# AtmoOrb.net
KiCad netlist of a schematic drawn in EAGLE
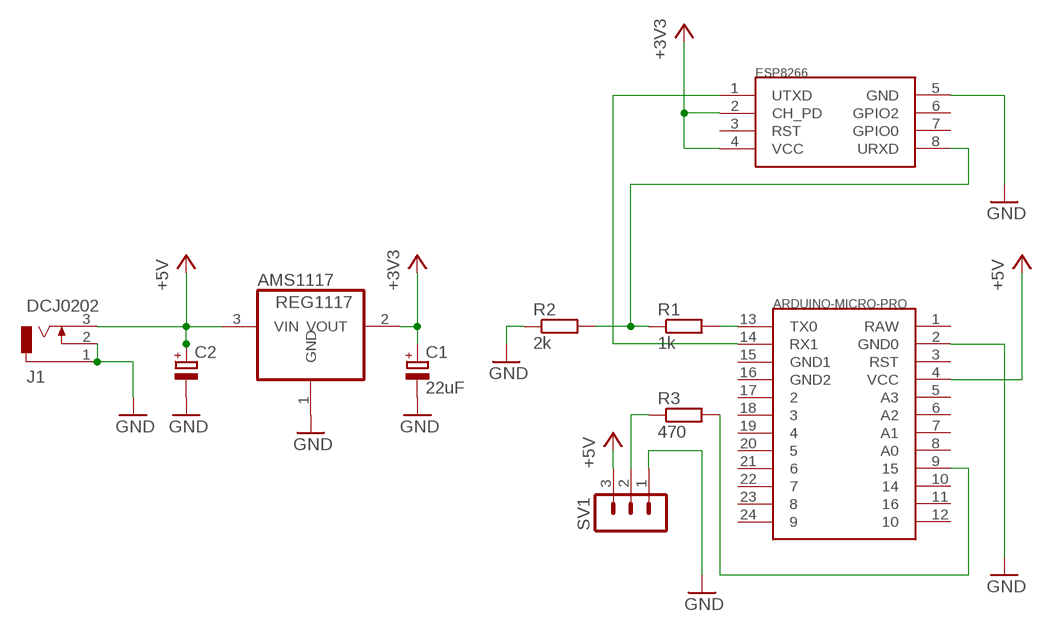
[diagram p0: schematic, sheet 1]

(export (version "E")
  (design (tool "Eeschema 10.0.6"))
  (components
    (comp (ref "AMS1117")
      (value "REG1117")
      (footprint "eagle-import:SOT223")
      (libsource (lib "eagle-import") (part "REG1117"))
    )
    (comp (ref "ARDUINO-MICRO-PRO")
      (value "ARDUINO_MICRO_PRO")
      (footprint "eagle-import:ARDUINO_MICRO_PRO")
      (libsource (lib "eagle-import") (part "ARDUINO_MICRO_PRO"))
    )
    (comp (ref "C1")
      (value "22uF")
      (footprint "eagle-import:TAP5-60")
      (libsource (lib "eagle-import") (part "CPOL-EUTAP5-60"))
    )
    (comp (ref "C2")
      (value "CPOL-EUTAP5-60")
      (footprint "eagle-import:TAP5-60")
      (libsource (lib "eagle-import") (part "CPOL-EUTAP5-60"))
    )
    (comp (ref "ESP8266")
      (value "ESP8266")
      (footprint "eagle-import:ESP8266")
      (libsource (lib "eagle-import") (part "ESP8266"))
    )
    (comp (ref "J1")
      (value "DCJ0202")
      (footprint "eagle-import:DCJ0202")
      (libsource (lib "eagle-import") (part "DCJ0202"))
    )
    (comp (ref "R1")
      (value "1k")
      (footprint "eagle-import:0207_10")
      (libsource (lib "eagle-import") (part "R-EU_0207/10"))
    )
    (comp (ref "R2")
      (value "2k")
      (footprint "eagle-import:0207_10")
      (libsource (lib "eagle-import") (part "R-EU_0207/10"))
    )
    (comp (ref "R3")
      (value "470")
      (footprint "eagle-import:0207_10")
      (libsource (lib "eagle-import") (part "R-EU_0207/10"))
    )
    (comp (ref "SV1")
      (value "MA03-1")
      (footprint "eagle-import:MA03-1")
      (libsource (lib "eagle-import") (part "MA03-1"))
    )
  )
  (nets
    (net (code "1") (name "+3V3") (class "Default")
      (node (ref "AMS1117") (pin "2") (pinfunction "VOUT_2") (pintype "output"))
      (node (ref "C1") (pin "+") (pinfunction "+_+") (pintype "passive"))
      (node (ref "ESP8266") (pin "2") (pinfunction "CH_PD_2") (pintype "bidirectional"))
      (node (ref "ESP8266") (pin "4") (pinfunction "VCC_4") (pintype "bidirectional"))
    )
    (net (code "2") (name "+5V") (class "Default")
      (node (ref "AMS1117") (pin "3") (pinfunction "VIN_3") (pintype "input"))
      (node (ref "ARDUINO-MICRO-PRO") (pin "4") (pinfunction "VCC_4") (pintype "bidirectional"))
      (node (ref "C2") (pin "+") (pinfunction "+_+") (pintype "passive"))
      (node (ref "J1") (pin "3") (pinfunction "3_3") (pintype "passive"))
      (node (ref "SV1") (pin "3") (pinfunction "3_3") (pintype "passive"))
    )
    (net (code "3") (name "GND") (class "Default")
      (node (ref "AMS1117") (pin "1") (pinfunction "GND_1") (pintype "power_in"))
      (node (ref "ARDUINO-MICRO-PRO") (pin "2") (pinfunction "GND0_2") (pintype "bidirectional"))
      (node (ref "C1") (pin "-") (pinfunction "-_-") (pintype "passive"))
      (node (ref "C2") (pin "-") (pinfunction "-_-") (pintype "passive"))
      (node (ref "ESP8266") (pin "5") (pinfunction "GND_5") (pintype "bidirectional"))
      (node (ref "J1") (pin "1") (pinfunction "1_1") (pintype "passive"))
      (node (ref "J1") (pin "2") (pinfunction "2_2") (pintype "passive"))
      (node (ref "R2") (pin "1") (pinfunction "1_1") (pintype "passive"))
      (node (ref "SV1") (pin "1") (pinfunction "1_1") (pintype "passive"))
    )
    (net (code "4") (name "Net-(ARDUINO-MICRO-PRO-15)") (class "Default")
      (node (ref "ARDUINO-MICRO-PRO") (pin "9") (pinfunction "15_9") (pintype "bidirectional"))
      (node (ref "R3") (pin "2") (pinfunction "2_2") (pintype "passive"))
    )
    (net (code "5") (name "Net-(ARDUINO-MICRO-PRO-RX1)") (class "Default")
      (node (ref "ARDUINO-MICRO-PRO") (pin "14") (pinfunction "RX1_14") (pintype "bidirectional"))
      (node (ref "ESP8266") (pin "1") (pinfunction "UTXD_1") (pintype "bidirectional"))
    )
    (net (code "6") (name "Net-(ARDUINO-MICRO-PRO-TX0)") (class "Default")
      (node (ref "ARDUINO-MICRO-PRO") (pin "13") (pinfunction "TX0_13") (pintype "bidirectional"))
      (node (ref "R1") (pin "2") (pinfunction "2_2") (pintype "passive"))
    )
    (net (code "7") (name "Net-(ESP8266-URXD)") (class "Default")
      (node (ref "ESP8266") (pin "8") (pinfunction "URXD_8") (pintype "bidirectional"))
      (node (ref "R1") (pin "1") (pinfunction "1_1") (pintype "passive"))
      (node (ref "R2") (pin "2") (pinfunction "2_2") (pintype "passive"))
    )
    (net (code "8") (name "Net-(R3-Pad1)") (class "Default")
      (node (ref "R3") (pin "1") (pinfunction "1_1") (pintype "passive"))
      (node (ref "SV1") (pin "2") (pinfunction "2_2") (pintype "passive"))
    )
    (net (code "9") (name "unconnected-(ARDUINO-MICRO-PRO-2-Pad17)") (class "Default")
      (node (ref "ARDUINO-MICRO-PRO") (pin "17") (pinfunction "2_17") (pintype "bidirectional"))
    )
    (net (code "10") (name "unconnected-(ARDUINO-MICRO-PRO-3-Pad18)") (class "Default")
      (node (ref "ARDUINO-MICRO-PRO") (pin "18") (pinfunction "3_18") (pintype "bidirectional"))
    )
    (net (code "11") (name "unconnected-(ARDUINO-MICRO-PRO-4-Pad19)") (class "Default")
      (node (ref "ARDUINO-MICRO-PRO") (pin "19") (pinfunction "4_19") (pintype "bidirectional"))
    )
    (net (code "12") (name "unconnected-(ARDUINO-MICRO-PRO-5-Pad20)") (class "Default")
      (node (ref "ARDUINO-MICRO-PRO") (pin "20") (pinfunction "5_20") (pintype "bidirectional"))
    )
    (net (code "13") (name "unconnected-(ARDUINO-MICRO-PRO-6-Pad21)") (class "Default")
      (node (ref "ARDUINO-MICRO-PRO") (pin "21") (pinfunction "6_21") (pintype "bidirectional"))
    )
    (net (code "14") (name "unconnected-(ARDUINO-MICRO-PRO-7-Pad22)") (class "Default")
      (node (ref "ARDUINO-MICRO-PRO") (pin "22") (pinfunction "7_22") (pintype "bidirectional"))
    )
    (net (code "15") (name "unconnected-(ARDUINO-MICRO-PRO-8-Pad23)") (class "Default")
      (node (ref "ARDUINO-MICRO-PRO") (pin "23") (pinfunction "8_23") (pintype "bidirectional"))
    )
    (net (code "16") (name "unconnected-(ARDUINO-MICRO-PRO-9-Pad24)") (class "Default")
      (node (ref "ARDUINO-MICRO-PRO") (pin "24") (pinfunction "9_24") (pintype "bidirectional"))
    )
    (net (code "17") (name "unconnected-(ARDUINO-MICRO-PRO-10-Pad12)") (class "Default")
      (node (ref "ARDUINO-MICRO-PRO") (pin "12") (pinfunction "10_12") (pintype "bidirectional"))
    )
    (net (code "18") (name "unconnected-(ARDUINO-MICRO-PRO-14-Pad10)") (class "Default")
      (node (ref "ARDUINO-MICRO-PRO") (pin "10") (pinfunction "14_10") (pintype "bidirectional"))
    )
    (net (code "19") (name "unconnected-(ARDUINO-MICRO-PRO-16-Pad11)") (class "Default")
      (node (ref "ARDUINO-MICRO-PRO") (pin "11") (pinfunction "16_11") (pintype "bidirectional"))
    )
    (net (code "20") (name "unconnected-(ARDUINO-MICRO-PRO-A0-Pad8)") (class "Default")
      (node (ref "ARDUINO-MICRO-PRO") (pin "8") (pinfunction "A0_8") (pintype "bidirectional"))
    )
    (net (code "21") (name "unconnected-(ARDUINO-MICRO-PRO-A1-Pad7)") (class "Default")
      (node (ref "ARDUINO-MICRO-PRO") (pin "7") (pinfunction "A1_7") (pintype "bidirectional"))
    )
    (net (code "22") (name "unconnected-(ARDUINO-MICRO-PRO-A2-Pad6)") (class "Default")
      (node (ref "ARDUINO-MICRO-PRO") (pin "6") (pinfunction "A2_6") (pintype "bidirectional"))
    )
    (net (code "23") (name "unconnected-(ARDUINO-MICRO-PRO-A3-Pad5)") (class "Default")
      (node (ref "ARDUINO-MICRO-PRO") (pin "5") (pinfunction "A3_5") (pintype "bidirectional"))
    )
    (net (code "24") (name "unconnected-(ARDUINO-MICRO-PRO-GND1-Pad15)") (class "Default")
      (node (ref "ARDUINO-MICRO-PRO") (pin "15") (pinfunction "GND1_15") (pintype "bidirectional"))
    )
    (net (code "25") (name "unconnected-(ARDUINO-MICRO-PRO-GND2-Pad16)") (class "Default")
      (node (ref "ARDUINO-MICRO-PRO") (pin "16") (pinfunction "GND2_16") (pintype "bidirectional"))
    )
    (net (code "26") (name "unconnected-(ARDUINO-MICRO-PRO-RAW-Pad1)") (class "Default")
      (node (ref "ARDUINO-MICRO-PRO") (pin "1") (pinfunction "RAW_1") (pintype "bidirectional"))
    )
    (net (code "27") (name "unconnected-(ARDUINO-MICRO-PRO-RST-Pad3)") (class "Default")
      (node (ref "ARDUINO-MICRO-PRO") (pin "3") (pinfunction "RST_3") (pintype "bidirectional"))
    )
    (net (code "28") (name "unconnected-(ESP8266-GPIO0-Pad7)") (class "Default")
      (node (ref "ESP8266") (pin "7") (pinfunction "GPIO0_7") (pintype "bidirectional"))
    )
    (net (code "29") (name "unconnected-(ESP8266-GPIO2-Pad6)") (class "Default")
      (node (ref "ESP8266") (pin "6") (pinfunction "GPIO2_6") (pintype "bidirectional"))
    )
    (net (code "30") (name "unconnected-(ESP8266-RST-Pad3)") (class "Default")
      (node (ref "ESP8266") (pin "3") (pinfunction "RST_3") (pintype "bidirectional"))
    )
  )
)
